# SparkFun_RTK_Facet_-_Main.net
KiCad netlist of a schematic drawn in EAGLE
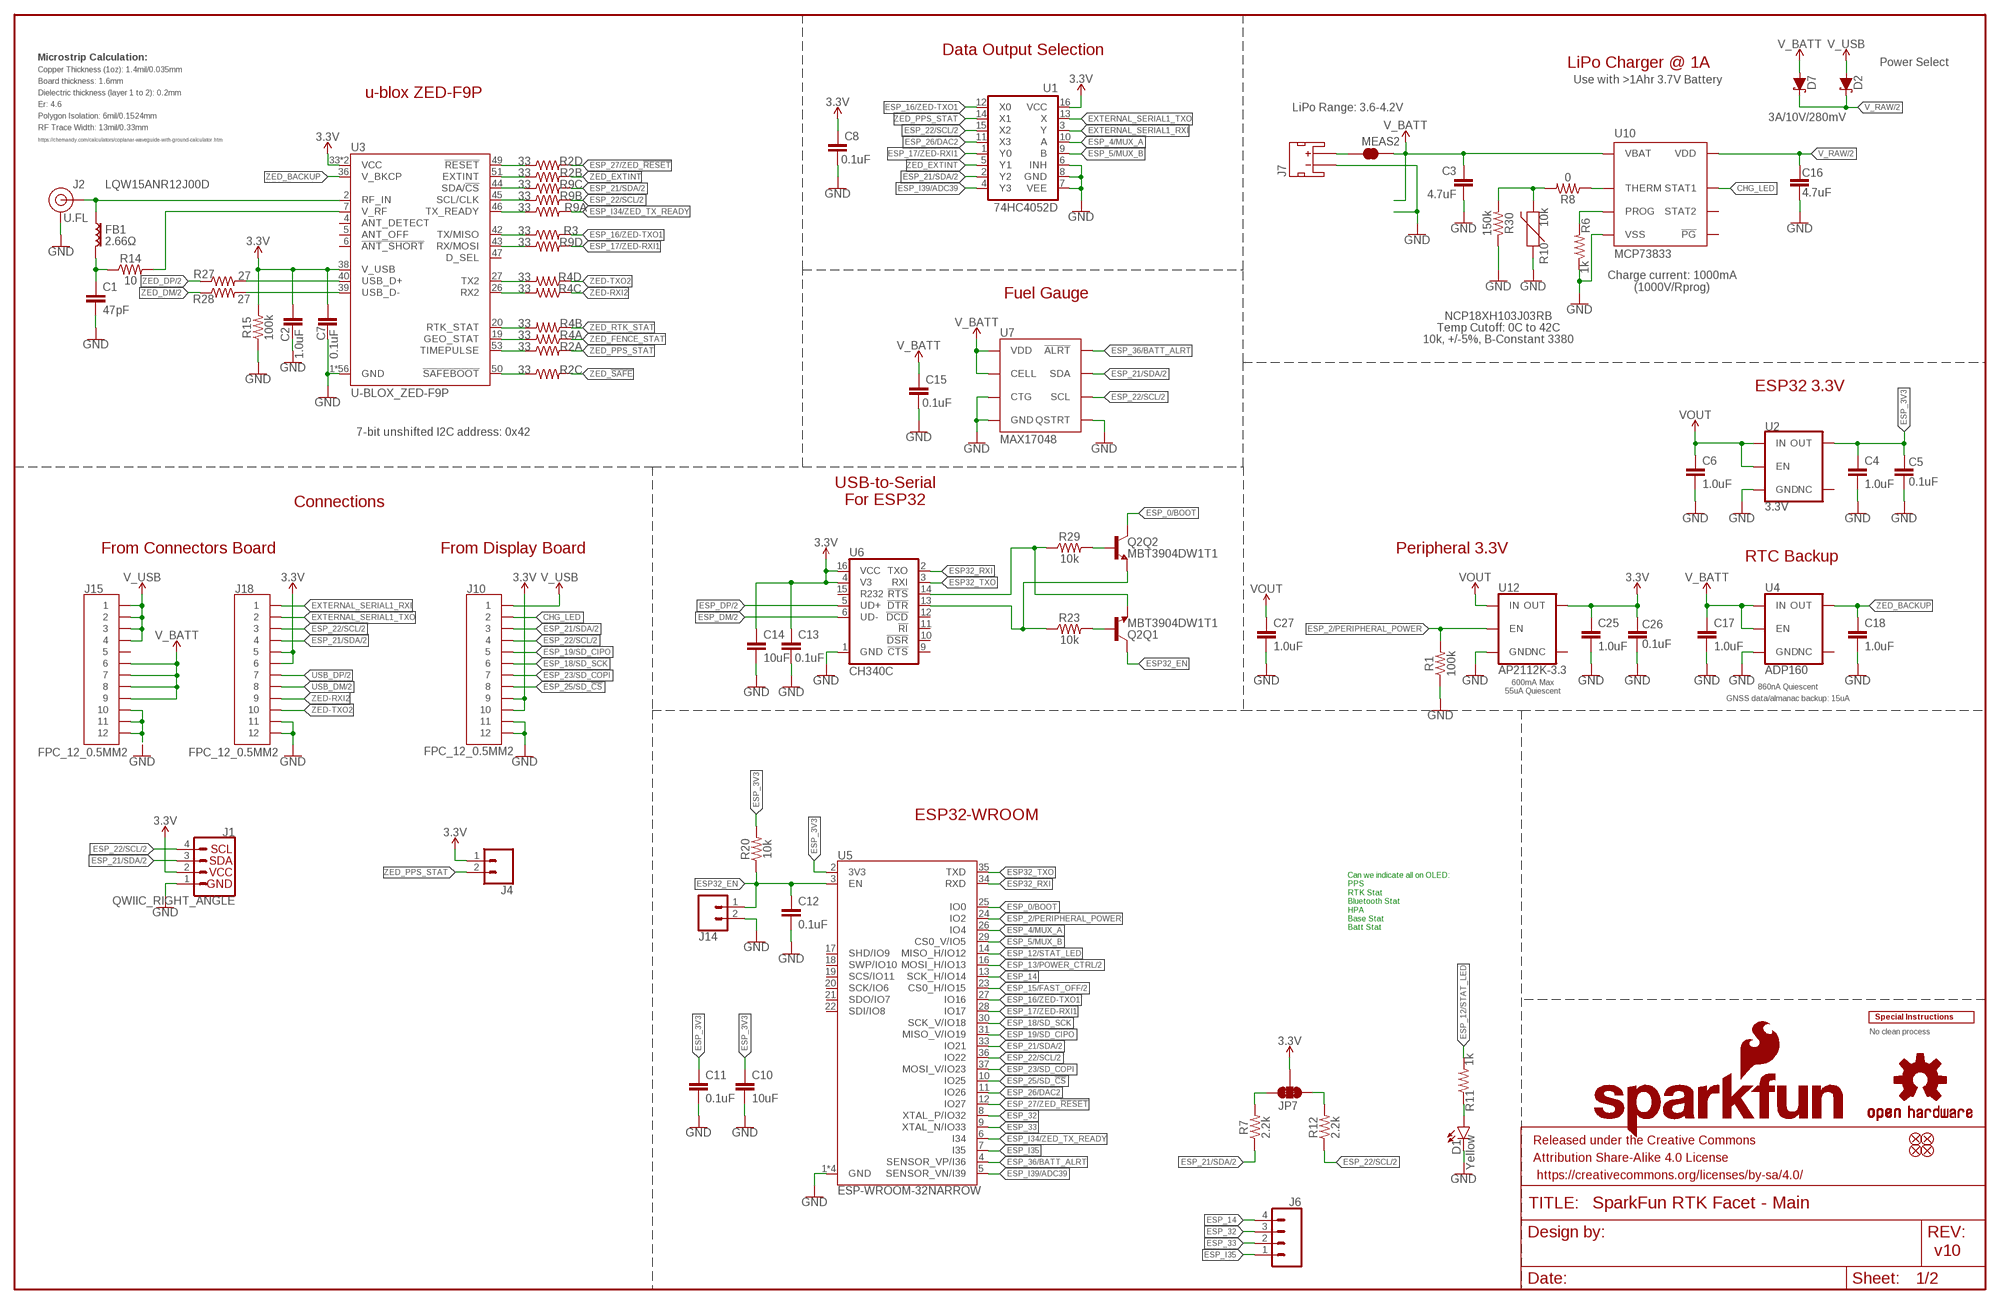
[diagram p0: schematic, sheet 1, part 1 of 2]
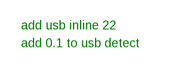
[diagram p1: schematic, sheet 1, part 2 of 2]
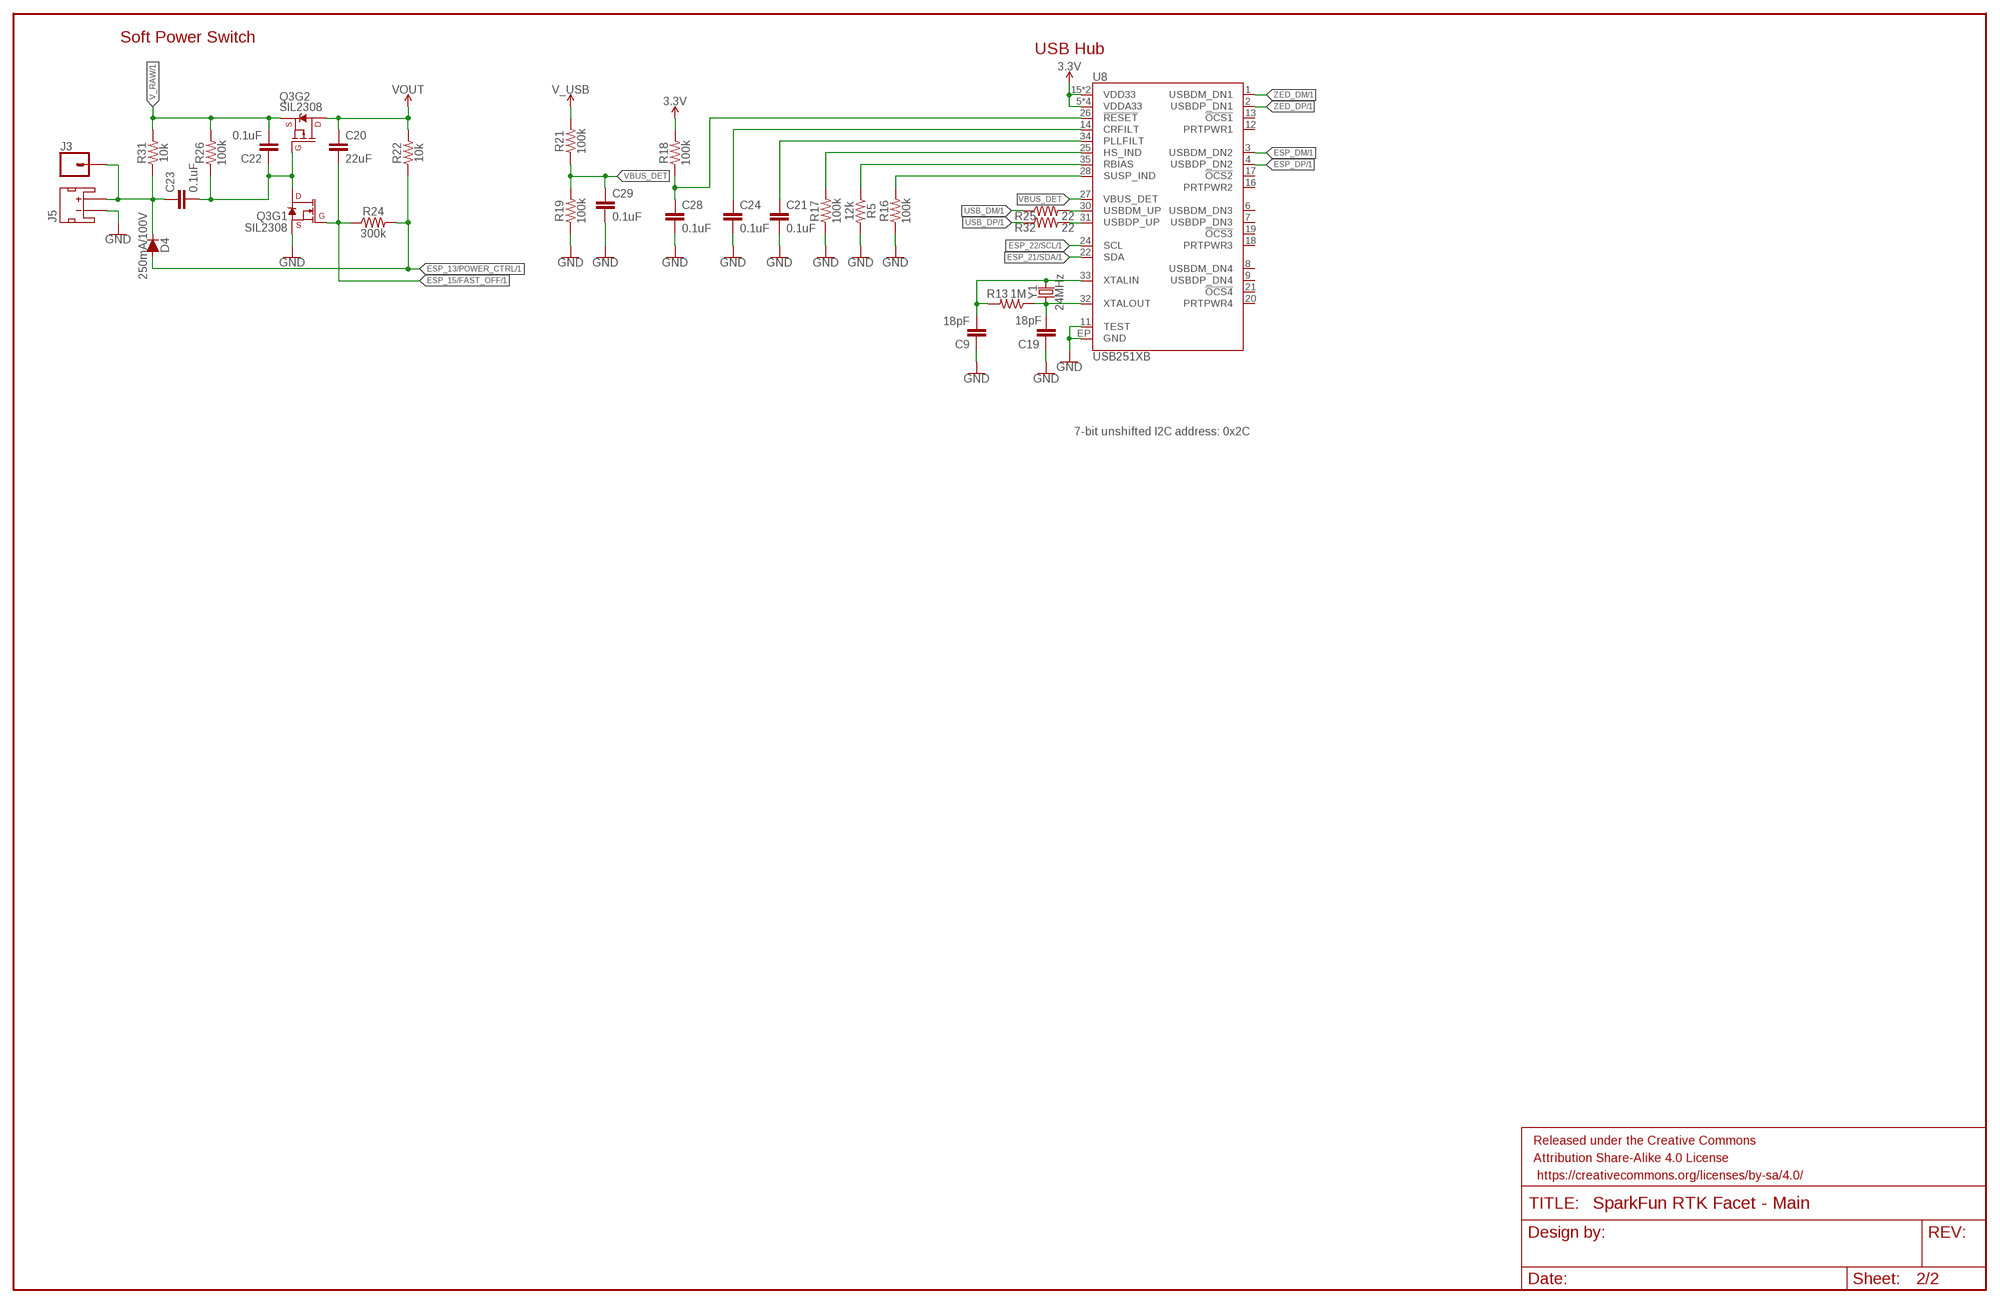
[diagram p2: schematic, sheet 2]

(export (version "E")
  (design (tool "Eeschema 10.0.6"))
  (components
    (comp (ref "C1")
      (value "47pF")
      (footprint "eagle-import:0402")
      (libsource (lib "eagle-import") (part "47PF-0402-25V-5%-X7R"))
    )
    (comp (ref "C2")
      (value "1.0uF")
      (footprint "eagle-import:0603")
      (libsource (lib "eagle-import") (part "1.0UF-0603-16V-10%-X7R"))
    )
    (comp (ref "C3")
      (value "4.7uF")
      (footprint "eagle-import:0603")
      (libsource (lib "eagle-import") (part "4.7UF-0603-35V-(20%)"))
    )
    (comp (ref "C4")
      (value "1.0uF")
      (footprint "eagle-import:0603")
      (libsource (lib "eagle-import") (part "1.0UF-0603-16V-10%-X7R"))
    )
    (comp (ref "C5")
      (value "0.1uF")
      (footprint "eagle-import:0603")
      (libsource (lib "eagle-import") (part "0.1UF-0603-25V-5%"))
    )
    (comp (ref "C6")
      (value "1.0uF")
      (footprint "eagle-import:0603")
      (libsource (lib "eagle-import") (part "1.0UF-0603-16V-10%-X7R"))
    )
    (comp (ref "C7")
      (value "0.1uF")
      (footprint "eagle-import:0603")
      (libsource (lib "eagle-import") (part "0.1UF-0603-25V-5%"))
    )
    (comp (ref "C8")
      (value "0.1uF")
      (footprint "eagle-import:0603")
      (libsource (lib "eagle-import") (part "0.1UF-0603-25V-(+80/-20%)"))
    )
    (comp (ref "C10")
      (value "10uF")
      (footprint "eagle-import:0603")
      (libsource (lib "eagle-import") (part "10UF-0603-6.3V-20%"))
    )
    (comp (ref "C11")
      (value "0.1uF")
      (footprint "eagle-import:0603")
      (libsource (lib "eagle-import") (part "0.1UF-0603-25V-(+80/-20%)"))
    )
    (comp (ref "C12")
      (value "0.1uF")
      (footprint "eagle-import:0603")
      (libsource (lib "eagle-import") (part "0.1UF-0603-25V-(+80/-20%)"))
    )
    (comp (ref "C13")
      (value "0.1uF")
      (footprint "eagle-import:0603")
      (libsource (lib "eagle-import") (part "0.1UF-0603-25V-(+80/-20%)"))
    )
    (comp (ref "C14")
      (value "10uF")
      (footprint "eagle-import:0603")
      (libsource (lib "eagle-import") (part "10UF-0603-6.3V-20%"))
    )
    (comp (ref "C15")
      (value "0.1uF")
      (footprint "eagle-import:0603")
      (libsource (lib "eagle-import") (part "0.1UF-0603-25V-(+80/-20%)"))
    )
    (comp (ref "C16")
      (value "4.7uF")
      (footprint "eagle-import:0603")
      (libsource (lib "eagle-import") (part "4.7UF-0603-35V-(20%)"))
    )
    (comp (ref "C17")
      (value "1.0uF")
      (footprint "eagle-import:0603")
      (libsource (lib "eagle-import") (part "1.0UF-0603-16V-10%-X7R"))
    )
    (comp (ref "C18")
      (value "1.0uF")
      (footprint "eagle-import:0603")
      (libsource (lib "eagle-import") (part "1.0UF-0603-16V-10%-X7R"))
    )
    (comp (ref "C25")
      (value "1.0uF")
      (footprint "eagle-import:0603")
      (libsource (lib "eagle-import") (part "1.0UF-0603-16V-10%-X7R"))
    )
    (comp (ref "C26")
      (value "0.1uF")
      (footprint "eagle-import:0603")
      (libsource (lib "eagle-import") (part "0.1UF-0603-25V-5%"))
    )
    (comp (ref "C27")
      (value "1.0uF")
      (footprint "eagle-import:0603")
      (libsource (lib "eagle-import") (part "1.0UF-0603-16V-10%-X7R"))
    )
    (comp (ref "D1")
      (value "Yellow")
      (footprint "eagle-import:LED-0603")
      (libsource (lib "eagle-import") (part "LED-YELLOW0603"))
    )
    (comp (ref "D2")
      (value "3A/10V/280mV")
      (footprint "eagle-import:SOD-323")
      (libsource (lib "eagle-import") (part "DIODE-SCHOTTKY-BAT60A"))
    )
    (comp (ref "D7")
      (value "3A/10V/280mV")
      (footprint "eagle-import:SOD-323")
      (libsource (lib "eagle-import") (part "DIODE-SCHOTTKY-BAT60A"))
    )
    (comp (ref "FB1")
      (value "2.66Ω")
      (footprint "eagle-import:0402-TIGHT")
      (libsource (lib "eagle-import") (part "FERRITE_BEAD-0402-2.66OHM-1GHZ"))
    )
    (comp (ref "FRAME2")
      (value "FRAME-LEDGER")
      (footprint "eagle-import:CREATIVE_COMMONS")
      (libsource (lib "eagle-import") (part "FRAME-LEDGER"))
    )
    (comp (ref "J1")
      (value "QWIIC_RIGHT_ANGLE")
      (footprint "eagle-import:JST04_1MM_RA")
      (libsource (lib "eagle-import") (part "QWIIC_CONNECTORJS-1MM"))
    )
    (comp (ref "J2")
      (value "U.FL")
      (footprint "eagle-import:U.FL")
      (libsource (lib "eagle-import") (part "U.FL2PIN"))
    )
    (comp (ref "J4")
      (value "CONN_021X02_NO_SILK")
      (footprint "eagle-import:1X02_NO_SILK")
      (libsource (lib "eagle-import") (part "CONN_021X02_NO_SILK"))
    )
    (comp (ref "J6")
      (value "CONN_041X04_NO_SILK_NO_POP")
      (footprint "eagle-import:1X04_NO_SILK")
      (libsource (lib "eagle-import") (part "CONN_041X04_NO_SILK_NO_POP"))
    )
    (comp (ref "J7")
      (value "JST_2MM_MALE")
      (footprint "eagle-import:JST-2-SMD")
      (libsource (lib "eagle-import") (part "JST_2MM_MALE"))
    )
    (comp (ref "J10")
      (value "FPC_12_0.5MM2")
      (footprint "eagle-import:FPC_12_FLIP_DOUBLESIDED_2")
      (libsource (lib "eagle-import") (part "FPC_12_0.5MM2"))
    )
    (comp (ref "J14")
      (value "CONN_021X02_NO_SILK")
      (footprint "eagle-import:1X02_NO_SILK")
      (libsource (lib "eagle-import") (part "CONN_021X02_NO_SILK"))
    )
    (comp (ref "J15")
      (value "FPC_12_0.5MM2")
      (footprint "eagle-import:FPC_12_FLIP_DOUBLESIDED_2")
      (libsource (lib "eagle-import") (part "FPC_12_0.5MM2"))
    )
    (comp (ref "J18")
      (value "FPC_12_0.5MM2")
      (footprint "eagle-import:FPC_12_FLIP_DOUBLESIDED_2")
      (libsource (lib "eagle-import") (part "FPC_12_0.5MM2"))
    )
    (comp (ref "JP7")
      (value "JUMPER-SMT_3_2-NC_TRACE_SILK")
      (footprint "eagle-import:SMT-JUMPER_3_2-NC_TRACE_SILK")
      (libsource (lib "eagle-import") (part "JUMPER-SMT_3_2-NC_TRACE_SILK"))
    )
    (comp (ref "JP21")
      (value "FIDUCIALUFIDUCIAL")
      (footprint "eagle-import:FIDUCIAL-MICRO")
      (libsource (lib "eagle-import") (part "FIDUCIALUFIDUCIAL"))
    )
    (comp (ref "JP61")
      (value "FIDUCIALUFIDUCIAL")
      (footprint "eagle-import:FIDUCIAL-MICRO")
      (libsource (lib "eagle-import") (part "FIDUCIALUFIDUCIAL"))
    )
    (comp (ref "JP71")
      (value "FIDUCIALUFIDUCIAL")
      (footprint "eagle-import:FIDUCIAL-MICRO")
      (libsource (lib "eagle-import") (part "FIDUCIALUFIDUCIAL"))
    )
    (comp (ref "JP81")
      (value "FIDUCIALUFIDUCIAL")
      (footprint "eagle-import:FIDUCIAL-MICRO")
      (libsource (lib "eagle-import") (part "FIDUCIALUFIDUCIAL"))
    )
    (comp (ref "LOGO1")
      (value "OSHW-LOGOMINI")
      (footprint "eagle-import:OSHW-LOGO-MINI")
      (libsource (lib "eagle-import") (part "OSHW-LOGOMINI"))
    )
    (comp (ref "LOGO2")
      (value "SFE_LOGO_NAME_FLAME.1_INCH")
      (footprint "eagle-import:SFE_LOGO_NAME_FLAME_.1")
      (libsource (lib "eagle-import") (part "SFE_LOGO_NAME_FLAME.1_INCH"))
    )
    (comp (ref "MEAS2")
      (value "JUMPER-COMBO_2_NC_TRACE")
      (footprint "eagle-import:COMBO-JUMPER_2_NC_TRACE")
      (libsource (lib "eagle-import") (part "JUMPER-COMBO_2_NC_TRACE"))
    )
    (comp (ref "Q2")
      (value "MBT3904DW1T1")
      (footprint "eagle-import:SC70-6")
      (libsource (lib "eagle-import") (part "TRANS_NPN_DUAL-MBT3904DW1T1"))
    )
    (comp (ref "R1")
      (value "100k")
      (footprint "eagle-import:0603")
      (libsource (lib "eagle-import") (part "100KOHM-0603-1/10W-1%"))
    )
    (comp (ref "R2")
      (value "33")
      (footprint "eagle-import:1206_RA")
      (libsource (lib "eagle-import") (part "33OHM_RA-1206-1/16W-5%"))
    )
    (comp (ref "R3")
      (value "33")
      (footprint "eagle-import:0603")
      (libsource (lib "eagle-import") (part "33OHM-0603-1/10W-1%"))
    )
    (comp (ref "R4")
      (value "33")
      (footprint "eagle-import:1206_RA")
      (libsource (lib "eagle-import") (part "33OHM_RA-1206-1/16W-5%"))
    )
    (comp (ref "R6")
      (value "1k")
      (footprint "eagle-import:0603")
      (libsource (lib "eagle-import") (part "1KOHM-0603-1/10W-1%"))
    )
    (comp (ref "R7")
      (value "2.2k")
      (footprint "eagle-import:0603")
      (libsource (lib "eagle-import") (part "2.2KOHM-0603-1/10W-1%"))
    )
    (comp (ref "R8")
      (value "0")
      (footprint "eagle-import:0603")
      (libsource (lib "eagle-import") (part "0OHM-0603-1/10W"))
    )
    (comp (ref "R9")
      (value "33")
      (footprint "eagle-import:1206_RA")
      (libsource (lib "eagle-import") (part "33OHM_RA-1206-1/16W-5%"))
    )
    (comp (ref "R10")
      (value "10k")
      (footprint "eagle-import:0603")
      (libsource (lib "eagle-import") (part "NTC-THERMISTOR-0603"))
    )
    (comp (ref "R11")
      (value "1k")
      (footprint "eagle-import:0603")
      (libsource (lib "eagle-import") (part "1KOHM-0603-1/10W-1%"))
    )
    (comp (ref "R12")
      (value "2.2k")
      (footprint "eagle-import:0603")
      (libsource (lib "eagle-import") (part "2.2KOHM-0603-1/10W-1%"))
    )
    (comp (ref "R14")
      (value "10")
      (footprint "eagle-import:0603")
      (libsource (lib "eagle-import") (part "10OHM-0603-1/10W-1%"))
    )
    (comp (ref "R15")
      (value "100k")
      (footprint "eagle-import:0603")
      (libsource (lib "eagle-import") (part "100KOHM-0603-1/10W-1%"))
    )
    (comp (ref "R20")
      (value "10k")
      (footprint "eagle-import:0603")
      (libsource (lib "eagle-import") (part "10KOHM-0603-1/10W-1%"))
    )
    (comp (ref "R23")
      (value "10k")
      (footprint "eagle-import:0603")
      (libsource (lib "eagle-import") (part "10KOHM-0603-1/10W-1%"))
    )
    (comp (ref "R27")
      (value "27")
      (footprint "eagle-import:0603")
      (libsource (lib "eagle-import") (part "27OHM-0603-1/10W-1%"))
    )
    (comp (ref "R28")
      (value "27")
      (footprint "eagle-import:0603")
      (libsource (lib "eagle-import") (part "27OHM-0603-1/10W-1%"))
    )
    (comp (ref "R29")
      (value "10k")
      (footprint "eagle-import:0603")
      (libsource (lib "eagle-import") (part "10KOHM-0603-1/10W-1%"))
    )
    (comp (ref "R30")
      (value "150k")
      (footprint "eagle-import:0603")
      (libsource (lib "eagle-import") (part "150KOHM-0603-1/10W-1%"))
    )
    (comp (ref "U$2")
      (value "SPECIAL_INSTRUCTIONS-ORDERING")
      (footprint "eagle-import:ORDERING_INSTRUCTIONS")
      (libsource (lib "eagle-import") (part "SPECIAL_INSTRUCTIONS-ORDERING"))
    )
    (comp (ref "U1")
      (value "74HC4052D")
      (footprint "eagle-import:SO16")
      (libsource (lib "eagle-import") (part "744052DHC"))
    )
    (comp (ref "U2")
      (value "3.3V")
      (footprint "eagle-import:SOT23-5")
      (libsource (lib "eagle-import") (part "V_REG_AP2112K-3.3V"))
    )
    (comp (ref "U3")
      (value "U-BLOX_ZED-F9P")
      (footprint "eagle-import:ZED-F9P")
      (libsource (lib "eagle-import") (part "U-BLOX_ZED-F9P"))
    )
    (comp (ref "U4")
      (value "ADP160")
      (footprint "eagle-import:SOT23-5")
      (libsource (lib "eagle-import") (part "ADP160"))
    )
    (comp (ref "U5")
      (value "ESP-WROOM-32NARROW")
      (footprint "eagle-import:ESP-WROOM-32-NARROW")
      (libsource (lib "eagle-import") (part "ESP-WROOM-32NARROW"))
    )
    (comp (ref "U6")
      (value "CH340C")
      (footprint "eagle-import:SO016")
      (libsource (lib "eagle-import") (part "CH340C"))
    )
    (comp (ref "U7")
      (value "MAX17048")
      (footprint "eagle-import:DFN-8")
      (libsource (lib "eagle-import") (part "MAX17048DFN8"))
    )
    (comp (ref "U10")
      (value "MCP73833")
      (footprint "eagle-import:DFN-10")
      (libsource (lib "eagle-import") (part "MCP73833"))
    )
    (comp (ref "U12")
      (value "AP2112K-3.3")
      (footprint "eagle-import:SOT23-5")
      (libsource (lib "eagle-import") (part "V_REG_AP2112K-3.3V"))
    )
    (comp (ref "C9")
      (value "18pF")
      (footprint "eagle-import:0603")
      (libsource (lib "eagle-import") (part "18PF-0603-50V-5%"))
    )
    (comp (ref "C19")
      (value "18pF")
      (footprint "eagle-import:0603")
      (libsource (lib "eagle-import") (part "18PF-0603-50V-5%"))
    )
    (comp (ref "C20")
      (value "22uF")
      (footprint "eagle-import:0603")
      (libsource (lib "eagle-import") (part "22UF-0603-6.3V-20%"))
    )
    (comp (ref "C21")
      (value "0.1uF")
      (footprint "eagle-import:0603")
      (libsource (lib "eagle-import") (part "0.1UF-0603-25V-5%"))
    )
    (comp (ref "C22")
      (value "0.1uF")
      (footprint "eagle-import:0603")
      (libsource (lib "eagle-import") (part "0.1UF-0603-25V-5%"))
    )
    (comp (ref "C23")
      (value "0.1uF")
      (footprint "eagle-import:0603")
      (libsource (lib "eagle-import") (part "0.1UF-0603-25V-5%"))
    )
    (comp (ref "C24")
      (value "0.1uF")
      (footprint "eagle-import:0603")
      (libsource (lib "eagle-import") (part "0.1UF-0603-25V-5%"))
    )
    (comp (ref "C28")
      (value "0.1uF")
      (footprint "eagle-import:0603")
      (libsource (lib "eagle-import") (part "0.1UF-0603-25V-5%"))
    )
    (comp (ref "C29")
      (value "0.1uF")
      (footprint "eagle-import:0603")
      (libsource (lib "eagle-import") (part "0.1UF-0603-25V-5%"))
    )
    (comp (ref "D4")
      (value "250mA/100V")
      (footprint "eagle-import:SOD-323")
      (libsource (lib "eagle-import") (part "DIODE-BAS16J"))
    )
    (comp (ref "FRAME1")
      (value "FRAME-LEDGER")
      (footprint "eagle-import:CREATIVE_COMMONS")
      (libsource (lib "eagle-import") (part "FRAME-LEDGER"))
    )
    (comp (ref "J3")
      (value "CONN_01PTH_NO_SILK_YES_STOP")
      (footprint "eagle-import:1X01_NO_SILK")
      (libsource (lib "eagle-import") (part "CONN_01PTH_NO_SILK_YES_STOP"))
    )
    (comp (ref "J5")
      (value "JST_2MM_MALE")
      (footprint "eagle-import:JST-2-SMD")
      (libsource (lib "eagle-import") (part "JST_2MM_MALE"))
    )
    (comp (ref "Q3")
      (value "SIL2308")
      (footprint "eagle-import:SOT26")
      (libsource (lib "eagle-import") (part "MOSFET_COMPLIMENTARY_PAIR-SIL2308"))
    )
    (comp (ref "R5")
      (value "12k")
      (footprint "eagle-import:0603")
      (libsource (lib "eagle-import") (part "12KOHM-0603-1/10W-1%"))
    )
    (comp (ref "R13")
      (value "1M")
      (footprint "eagle-import:0603")
      (libsource (lib "eagle-import") (part "1MOHM-0603-1/4W-5%"))
    )
    (comp (ref "R16")
      (value "100k")
      (footprint "eagle-import:0603")
      (libsource (lib "eagle-import") (part "100KOHM-0603-1/10W-1%"))
    )
    (comp (ref "R17")
      (value "100k")
      (footprint "eagle-import:0603")
      (libsource (lib "eagle-import") (part "100KOHM-0603-1/10W-1%"))
    )
    (comp (ref "R18")
      (value "100k")
      (footprint "eagle-import:0603")
      (libsource (lib "eagle-import") (part "100KOHM-0603-1/10W-1%"))
    )
    (comp (ref "R19")
      (value "100k")
      (footprint "eagle-import:0603")
      (libsource (lib "eagle-import") (part "100KOHM-0603-1/10W-1%"))
    )
    (comp (ref "R21")
      (value "100k")
      (footprint "eagle-import:0603")
      (libsource (lib "eagle-import") (part "100KOHM-0603-1/10W-1%"))
    )
    (comp (ref "R22")
      (value "10k")
      (footprint "eagle-import:0603")
      (libsource (lib "eagle-import") (part "10KOHM-0603-1/10W-1%"))
    )
    (comp (ref "R24")
      (value "300k")
      (footprint "eagle-import:0603")
      (libsource (lib "eagle-import") (part "300KOHM-0603-1/10W-1%"))
    )
    (comp (ref "R25")
      (value "22")
      (footprint "eagle-import:0603")
      (libsource (lib "eagle-import") (part "22OHM-0603-1/10W-1%"))
    )
    (comp (ref "R26")
      (value "100k")
      (footprint "eagle-import:0603")
      (libsource (lib "eagle-import") (part "100KOHM-0603-1/10W-1%"))
    )
    (comp (ref "R31")
      (value "10k")
      (footprint "eagle-import:0603")
      (libsource (lib "eagle-import") (part "10KOHM-0603-1/10W-1%"))
    )
    (comp (ref "R32")
      (value "22")
      (footprint "eagle-import:0603")
      (libsource (lib "eagle-import") (part "22OHM-0603-1/10W-1%"))
    )
    (comp (ref "U8")
      (value "USB251XB")
      (footprint "eagle-import:QFN-36")
      (libsource (lib "eagle-import") (part "USB251XB"))
    )
    (comp (ref "Y1")
      (value "24MHz")
      (footprint "eagle-import:CRYSTAL-SMD-2.0X1.6MM")
      (libsource (lib "eagle-import") (part "CRYSTAL-24MHZ-SMD-2.0X1.6MM"))
    )
  )
  (nets
    (net (code "1") (name "3.3V") (class "Default")
      (node (ref "C13") (pin "1") (pinfunction "1_1") (pintype "passive"))
      (node (ref "C14") (pin "1") (pinfunction "1_1") (pintype "passive"))
      (node (ref "C2") (pin "1") (pinfunction "1_1") (pintype "passive"))
      (node (ref "C25") (pin "1") (pinfunction "1_1") (pintype "passive"))
      (node (ref "C26") (pin "2") (pinfunction "2_2") (pintype "passive"))
      (node (ref "C7") (pin "2") (pinfunction "2_2") (pintype "passive"))
      (node (ref "C8") (pin "1") (pinfunction "1_1") (pintype "passive"))
      (node (ref "J1") (pin "2") (pinfunction "2_2") (pintype "power_in"))
      (node (ref "J10") (pin "10") (pinfunction "10_10") (pintype "bidirectional"))
      (node (ref "J10") (pin "9") (pinfunction "9_9") (pintype "bidirectional"))
      (node (ref "J18") (pin "5") (pinfunction "5_5") (pintype "bidirectional"))
      (node (ref "J18") (pin "6") (pinfunction "6_6") (pintype "bidirectional"))
      (node (ref "J4") (pin "1") (pinfunction "1_1") (pintype "passive"))
      (node (ref "JP7") (pin "2") (pinfunction "2_2") (pintype "passive"))
      (node (ref "R15") (pin "2") (pinfunction "2_2") (pintype "passive"))
      (node (ref "R18") (pin "2") (pinfunction "2_2") (pintype "passive"))
      (node (ref "U1") (pin "16") (pinfunction "VCC_16") (pintype "power_in"))
      (node (ref "U12") (pin "5") (pinfunction "OUT_5") (pintype "passive"))
      (node (ref "U3") (pin "33") (pinfunction "VCC_33") (pintype "bidirectional"))
      (node (ref "U3") (pin "34") (pinfunction "VCC_34") (pintype "bidirectional"))
      (node (ref "U3") (pin "38") (pinfunction "V_USB_38") (pintype "bidirectional"))
      (node (ref "U6") (pin "16") (pinfunction "VCC_16") (pintype "bidirectional"))
      (node (ref "U6") (pin "4") (pinfunction "V3_4") (pintype "bidirectional"))
      (node (ref "U8") (pin "10") (pinfunction "VDDA33_10") (pintype "bidirectional"))
      (node (ref "U8") (pin "15") (pinfunction "VDD33_15") (pintype "bidirectional"))
      (node (ref "U8") (pin "23") (pinfunction "VDD33_23") (pintype "bidirectional"))
      (node (ref "U8") (pin "29") (pinfunction "VDDA33_29") (pintype "bidirectional"))
      (node (ref "U8") (pin "36") (pinfunction "VDDA33_36") (pintype "bidirectional"))
      (node (ref "U8") (pin "5") (pinfunction "VDDA33_5") (pintype "bidirectional"))
    )
    (net (code "2") (name "CHG_LED") (class "Default")
      (node (ref "J10") (pin "2") (pinfunction "2_2") (pintype "bidirectional"))
      (node (ref "U10") (pin "3") (pinfunction "STAT1_3") (pintype "bidirectional"))
    )
    (net (code "3") (name "ESP32_EN") (class "Default")
      (node (ref "C12") (pin "1") (pinfunction "1_1") (pintype "passive"))
      (node (ref "J14") (pin "1") (pinfunction "1_1") (pintype "passive"))
      (node (ref "Q2") (pin "3") (pinfunction "C_3") (pintype "passive"))
      (node (ref "R20") (pin "1") (pinfunction "1_1") (pintype "passive"))
      (node (ref "U5") (pin "3") (pinfunction "EN_3") (pintype "bidirectional"))
    )
    (net (code "4") (name "ESP32_RXI") (class "Default")
      (node (ref "U5") (pin "34") (pinfunction "RXD_34") (pintype "bidirectional"))
      (node (ref "U6") (pin "2") (pinfunction "TXO_2") (pintype "bidirectional"))
    )
    (net (code "5") (name "ESP32_TXO") (class "Default")
      (node (ref "U5") (pin "35") (pinfunction "TXD_35") (pintype "bidirectional"))
      (node (ref "U6") (pin "3") (pinfunction "RXI_3") (pintype "bidirectional"))
    )
    (net (code "6") (name "ESP_0{slash}BOOT") (class "Default")
      (node (ref "Q2") (pin "6") (pinfunction "C_6") (pintype "passive"))
      (node (ref "U5") (pin "25") (pinfunction "IO0_25") (pintype "bidirectional"))
    )
    (net (code "7") (name "ESP_2{slash}PERIPHERAL_POWER") (class "Default")
      (node (ref "R1") (pin "2") (pinfunction "2_2") (pintype "passive"))
      (node (ref "U12") (pin "3") (pinfunction "EN_3") (pintype "input"))
      (node (ref "U5") (pin "24") (pinfunction "IO2_24") (pintype "bidirectional"))
    )
    (net (code "8") (name "ESP_3V3") (class "Default")
      (node (ref "C10") (pin "1") (pinfunction "1_1") (pintype "passive"))
      (node (ref "C11") (pin "1") (pinfunction "1_1") (pintype "passive"))
      (node (ref "C4") (pin "1") (pinfunction "1_1") (pintype "passive"))
      (node (ref "C5") (pin "2") (pinfunction "2_2") (pintype "passive"))
      (node (ref "R20") (pin "2") (pinfunction "2_2") (pintype "passive"))
      (node (ref "U2") (pin "5") (pinfunction "OUT_5") (pintype "passive"))
      (node (ref "U5") (pin "2") (pinfunction "3V3_2") (pintype "bidirectional"))
    )
    (net (code "9") (name "ESP_4{slash}MUX_A") (class "Default")
      (node (ref "U1") (pin "10") (pinfunction "A_10") (pintype "input"))
      (node (ref "U5") (pin "26") (pinfunction "IO4_26") (pintype "bidirectional"))
    )
    (net (code "10") (name "ESP_5{slash}MUX_B") (class "Default")
      (node (ref "U1") (pin "9") (pinfunction "B_9") (pintype "input"))
      (node (ref "U5") (pin "29") (pinfunction "CS0_V/IO5_29") (pintype "bidirectional"))
    )
    (net (code "11") (name "ESP_12{slash}STAT_LED") (class "Default")
      (node (ref "R11") (pin "2") (pinfunction "2_2") (pintype "passive"))
      (node (ref "U5") (pin "14") (pinfunction "MISO_H/IO12_14") (pintype "bidirectional"))
    )
    (net (code "12") (name "ESP_13{slash}POWER_CTRL") (class "Default")
      (node (ref "D4") (pin "A") (pinfunction "A_A") (pintype "passive"))
      (node (ref "R22") (pin "1") (pinfunction "1_1") (pintype "passive"))
      (node (ref "R24") (pin "2") (pinfunction "2_2") (pintype "passive"))
      (node (ref "U5") (pin "16") (pinfunction "MOSI_H/IO13_16") (pintype "bidirectional"))
    )
    (net (code "13") (name "ESP_14") (class "Default")
      (node (ref "J6") (pin "4") (pinfunction "4_4") (pintype "passive"))
      (node (ref "U5") (pin "13") (pinfunction "SCK_H/IO14_13") (pintype "bidirectional"))
    )
    (net (code "14") (name "ESP_15{slash}FAST_OFF") (class "Default")
      (node (ref "C20") (pin "2") (pinfunction "2_2") (pintype "passive"))
      (node (ref "Q3") (pin "G1") (pinfunction "G_G1") (pintype "bidirectional"))
      (node (ref "R24") (pin "1") (pinfunction "1_1") (pintype "passive"))
      (node (ref "U5") (pin "23") (pinfunction "CS0_H/IO15_23") (pintype "bidirectional"))
    )
    (net (code "15") (name "ESP_16{slash}ZED-TXO1") (class "Default")
      (node (ref "R3") (pin "2") (pinfunction "2_2") (pintype "passive"))
      (node (ref "U1") (pin "12") (pinfunction "X0_12") (pintype "bidirectional"))
      (node (ref "U5") (pin "27") (pinfunction "IO16_27") (pintype "bidirectional"))
    )
    (net (code "16") (name "ESP_17{slash}ZED-RXI1") (class "Default")
      (node (ref "R9") (pin "P5") (pinfunction "2_P5") (pintype "passive"))
      (node (ref "U1") (pin "1") (pinfunction "Y0_1") (pintype "bidirectional"))
      (node (ref "U5") (pin "28") (pinfunction "IO17_28") (pintype "bidirectional"))
    )
    (net (code "17") (name "ESP_18{slash}SD_SCK") (class "Default")
      (node (ref "J10") (pin "6") (pinfunction "6_6") (pintype "bidirectional"))
      (node (ref "U5") (pin "30") (pinfunction "SCK_V/IO18_30") (pintype "bidirectional"))
    )
    (net (code "18") (name "ESP_19{slash}SD_CIPO") (class "Default")
      (node (ref "J10") (pin "5") (pinfunction "5_5") (pintype "bidirectional"))
      (node (ref "U5") (pin "31") (pinfunction "MISO_V/IO19_31") (pintype "bidirectional"))
    )
    (net (code "19") (name "ESP_21{slash}SDA") (class "Default")
      (node (ref "J1") (pin "3") (pinfunction "3_3") (pintype "passive"))
      (node (ref "J10") (pin "3") (pinfunction "3_3") (pintype "bidirectional"))
      (node (ref "J18") (pin "4") (pinfunction "4_4") (pintype "bidirectional"))
      (node (ref "R7") (pin "1") (pinfunction "1_1") (pintype "passive"))
      (node (ref "R9") (pin "P6") (pinfunction "2_P6") (pintype "passive"))
      (node (ref "U1") (pin "2") (pinfunction "Y2_2") (pintype "bidirectional"))
      (node (ref "U5") (pin "33") (pinfunction "IO21_33") (pintype "bidirectional"))
      (node (ref "U7") (pin "8") (pinfunction "SDA_8") (pintype "input"))
      (node (ref "U8") (pin "22") (pinfunction "SDA_22") (pintype "bidirectional"))
    )
    (net (code "20") (name "ESP_22{slash}SCL") (class "Default")
      (node (ref "J1") (pin "4") (pinfunction "4_4") (pintype "passive"))
      (node (ref "J10") (pin "4") (pinfunction "4_4") (pintype "bidirectional"))
      (node (ref "J18") (pin "3") (pinfunction "3_3") (pintype "bidirectional"))
      (node (ref "R12") (pin "1") (pinfunction "1_1") (pintype "passive"))
      (node (ref "R9") (pin "P7") (pinfunction "2_P7") (pintype "passive"))
      (node (ref "U1") (pin "15") (pinfunction "X2_15") (pintype "bidirectional"))
      (node (ref "U5") (pin "36") (pinfunction "IO22_36") (pintype "bidirectional"))
      (node (ref "U7") (pin "7") (pinfunction "SCL_7") (pintype "output"))
      (node (ref "U8") (pin "24") (pinfunction "SCL_24") (pintype "bidirectional"))
    )
    (net (code "21") (name "ESP_23{slash}SD_COPI") (class "Default")
      (node (ref "J10") (pin "7") (pinfunction "7_7") (pintype "bidirectional"))
      (node (ref "U5") (pin "37") (pinfunction "MOSI_V/IO23_37") (pintype "bidirectional"))
    )
    (net (code "22") (name "ESP_25{slash}SD_~{CS}") (class "Default")
      (node (ref "J10") (pin "8") (pinfunction "8_8") (pintype "bidirectional"))
      (node (ref "U5") (pin "10") (pinfunction "IO25_10") (pintype "bidirectional"))
    )
    (net (code "23") (name "ESP_26{slash}DAC2") (class "Default")
      (node (ref "U1") (pin "11") (pinfunction "X3_11") (pintype "bidirectional"))
      (node (ref "U5") (pin "11") (pinfunction "IO26_11") (pintype "bidirectional"))
    )
    (net (code "24") (name "ESP_27{slash}ZED_~{RESET}") (class "Default")
      (node (ref "R2") (pin "P5") (pinfunction "2_P5") (pintype "passive"))
      (node (ref "U5") (pin "12") (pinfunction "IO27_12") (pintype "bidirectional"))
    )
    (net (code "25") (name "ESP_32") (class "Default")
      (node (ref "J6") (pin "3") (pinfunction "3_3") (pintype "passive"))
      (node (ref "U5") (pin "8") (pinfunction "XTAL_P/IO32_8") (pintype "bidirectional"))
    )
    (net (code "26") (name "ESP_33") (class "Default")
      (node (ref "J6") (pin "2") (pinfunction "2_2") (pintype "passive"))
      (node (ref "U5") (pin "9") (pinfunction "XTAL_N/IO33_9") (pintype "bidirectional"))
    )
    (net (code "27") (name "ESP_36{slash}BATT_ALRT") (class "Default")
      (node (ref "U5") (pin "4") (pinfunction "SENSOR_VP/I36_4") (pintype "bidirectional"))
      (node (ref "U7") (pin "5") (pinfunction "~{ALRT}_5") (pintype "bidirectional"))
    )
    (net (code "28") (name "ESP_DM") (class "Default")
      (node (ref "U6") (pin "6") (pinfunction "UD-_6") (pintype "bidirectional"))
      (node (ref "U8") (pin "3") (pinfunction "USBDM_DN2_3") (pintype "bidirectional"))
    )
    (net (code "29") (name "ESP_DP") (class "Default")
      (node (ref "U6") (pin "5") (pinfunction "UD+_5") (pintype "bidirectional"))
      (node (ref "U8") (pin "4") (pinfunction "USBDP_DN2_4") (pintype "bidirectional"))
    )
    (net (code "30") (name "ESP_I34{slash}ZED_TX_READY") (class "Default")
      (node (ref "R9") (pin "P8") (pinfunction "2_P8") (pintype "passive"))
      (node (ref "U5") (pin "6") (pinfunction "I34_6") (pintype "bidirectional"))
    )
    (net (code "31") (name "ESP_I35") (class "Default")
      (node (ref "J6") (pin "1") (pinfunction "1_1") (pintype "passive"))
      (node (ref "U5") (pin "7") (pinfunction "I35_7") (pintype "bidirectional"))
    )
    (net (code "32") (name "ESP_I39{slash}ADC39") (class "Default")
      (node (ref "U1") (pin "4") (pinfunction "Y3_4") (pintype "bidirectional"))
      (node (ref "U5") (pin "5") (pinfunction "SENSOR_VN/I39_5") (pintype "bidirectional"))
    )
    (net (code "33") (name "EXTERNAL_SERIAL1_RXI") (class "Default")
      (node (ref "J18") (pin "1") (pinfunction "1_1") (pintype "bidirectional"))
      (node (ref "U1") (pin "3") (pinfunction "Y_3") (pintype "bidirectional"))
    )
    (net (code "34") (name "EXTERNAL_SERIAL1_TXO") (class "Default")
      (node (ref "J18") (pin "2") (pinfunction "2_2") (pintype "bidirectional"))
      (node (ref "U1") (pin "13") (pinfunction "X_13") (pintype "bidirectional"))
    )
    (net (code "35") (name "GND") (class "Default")
      (node (ref "C1") (pin "2") (pinfunction "2_2") (pintype "passive"))
      (node (ref "C10") (pin "2") (pinfunction "2_2") (pintype "passive"))
      (node (ref "C11") (pin "2") (pinfunction "2_2") (pintype "passive"))
      (node (ref "C12") (pin "2") (pinfunction "2_2") (pintype "passive"))
      (node (ref "C13") (pin "2") (pinfunction "2_2") (pintype "passive"))
      (node (ref "C14") (pin "2") (pinfunction "2_2") (pintype "passive"))
      (node (ref "C15") (pin "2") (pinfunction "2_2") (pintype "passive"))
      (node (ref "C16") (pin "2") (pinfunction "2_2") (pintype "passive"))
      (node (ref "C17") (pin "2") (pinfunction "2_2") (pintype "passive"))
      (node (ref "C18") (pin "2") (pinfunction "2_2") (pintype "passive"))
      (node (ref "C19") (pin "1") (pinfunction "1_1") (pintype "passive"))
      (node (ref "C2") (pin "2") (pinfunction "2_2") (pintype "passive"))
      (node (ref "C21") (pin "2") (pinfunction "2_2") (pintype "passive"))
      (node (ref "C24") (pin "2") (pinfunction "2_2") (pintype "passive"))
      (node (ref "C25") (pin "2") (pinfunction "2_2") (pintype "passive"))
      (node (ref "C26") (pin "1") (pinfunction "1_1") (pintype "passive"))
      (node (ref "C27") (pin "2") (pinfunction "2_2") (pintype "passive"))
      (node (ref "C28") (pin "2") (pinfunction "2_2") (pintype "passive"))
      (node (ref "C29") (pin "2") (pinfunction "2_2") (pintype "passive"))
      (node (ref "C3") (pin "2") (pinfunction "2_2") (pintype "passive"))
      (node (ref "C4") (pin "2") (pinfunction "2_2") (pintype "passive"))
      (node (ref "C5") (pin "1") (pinfunction "1_1") (pintype "passive"))
      (node (ref "C6") (pin "2") (pinfunction "2_2") (pintype "passive"))
      (node (ref "C7") (pin "1") (pinfunction "1_1") (pintype "passive"))
      (node (ref "C8") (pin "2") (pinfunction "2_2") (pintype "passive"))
      (node (ref "C9") (pin "1") (pinfunction "1_1") (pintype "passive"))
      (node (ref "D1") (pin "C") (pinfunction "C_C") (pintype "passive"))
      (node (ref "J1") (pin "1") (pinfunction "1_1") (pintype "power_in"))
      (node (ref "J10") (pin "11") (pinfunction "11_11") (pintype "bidirectional"))
      (node (ref "J10") (pin "12") (pinfunction "12_12") (pintype "bidirectional"))
      (node (ref "J14") (pin "2") (pinfunction "2_2") (pintype "passive"))
      (node (ref "J15") (pin "10") (pinfunction "10_10") (pintype "bidirectional"))
      (node (ref "J15") (pin "11") (pinfunction "11_11") (pintype "bidirectional"))
      (node (ref "J15") (pin "12") (pinfunction "12_12") (pintype "bidirectional"))
      (node (ref "J18") (pin "11") (pinfunction "11_11") (pintype "bidirectional"))
      (node (ref "J18") (pin "12") (pinfunction "12_12") (pintype "bidirectional"))
      (node (ref "J2") (pin "1") (pinfunction "GND_1") (pintype "bidirectional"))
      (node (ref "J2") (pin "2") (pinfunction "GND_2") (pintype "bidirectional"))
      (node (ref "J5") (pin "1") (pinfunction "-_1") (pintype "bidirectional"))
      (node (ref "J7") (pin "1") (pinfunction "-_1") (pintype "bidirectional"))
      (node (ref "Q3") (pin "S1") (pinfunction "S_S1") (pintype "bidirectional"))
      (node (ref "R1") (pin "1") (pinfunction "1_1") (pintype "passive"))
      (node (ref "R10") (pin "1") (pinfunction "1_1") (pintype "bidirectional"))
      (node (ref "R15") (pin "1") (pinfunction "1_1") (pintype "passive"))
      (node (ref "R16") (pin "1") (pinfunction "1_1") (pintype "passive"))
      (node (ref "R17") (pin "1") (pinfunction "1_1") (pintype "passive"))
      (node (ref "R19") (pin "1") (pinfunction "1_1") (pintype "passive"))
      (node (ref "R30") (pin "1") (pinfunction "1_1") (pintype "passive"))
      (node (ref "R5") (pin "2") (pinfunction "2_2") (pintype "passive"))
      (node (ref "R6") (pin "1") (pinfunction "1_1") (pintype "passive"))
      (node (ref "U1") (pin "6") (pinfunction "INH_6") (pintype "input"))
      (node (ref "U1") (pin "7") (pinfunction "VEE_7") (pintype "power_in"))
      (node (ref "U1") (pin "8") (pinfunction "GND_8") (pintype "power_in"))
      (node (ref "U10") (pin "11") (pinfunction "VSS_11") (pintype "bidirectional"))
      (node (ref "U10") (pin "5") (pinfunction "VSS_5") (pintype "bidirectional"))
      (node (ref "U12") (pin "2") (pinfunction "GND_2") (pintype "input"))
      (node (ref "U2") (pin "2") (pinfunction "GND_2") (pintype "input"))
      (node (ref "U3") (pin "1") (pinfunction "GND_1") (pintype "bidirectional"))
      (node (ref "U3") (pin "100") (pinfunction "GND_100") (pintype "bidirectional"))
      (node (ref "U3") (pin "101") (pinfunction "GND_101") (pintype "bidirectional"))
      (node (ref "U3") (pin "102") (pinfunction "GND_102") (pintype "bidirectional"))
      (node (ref "U3") (pin "12") (pinfunction "GND_12") (pintype "bidirectional"))
      (node (ref "U3") (pin "14") (pinfunction "GND_14") (pintype "bidirectional"))
      (node (ref "U3") (pin "3") (pinfunction "GND_3") (pintype "bidirectional"))
      (node (ref "U3") (pin "32") (pinfunction "GND_32") (pintype "bidirectional"))
      (node (ref "U3") (pin "37") (pinfunction "GND_37") (pintype "bidirectional"))
      (node (ref "U3") (pin "41") (pinfunction "GND_41") (pintype "bidirectional"))
      (node (ref "U3") (pin "48") (pinfunction "GND_48") (pintype "bidirectional"))
      (node (ref "U3") (pin "55") (pinfunction "GND_55") (pintype "bidirectional"))
      (node (ref "U3") (pin "56") (pinfunction "GND_56") (pintype "bidirectional"))
      (node (ref "U3") (pin "57") (pinfunction "GND_57") (pintype "bidirectional"))
      (node (ref "U3") (pin "58") (pinfunction "GND_58") (pintype "bidirectional"))
      (node (ref "U3") (pin "59") (pinfunction "GND_59") (pintype "bidirectional"))
      (node (ref "U3") (pin "60") (pinfunction "GND_60") (pintype "bidirectional"))
      (node (ref "U3") (pin "61") (pinfunction "GND_61") (pintype "bidirectional"))
      (node (ref "U3") (pin "62") (pinfunction "GND_62") (pintype "bidirectional"))
      (node (ref "U3") (pin "63") (pinfunction "GND_63") (pintype "bidirectional"))
      (node (ref "U3") (pin "64") (pinfunction "GND_64") (pintype "bidirectional"))
      (node (ref "U3") (pin "65") (pinfunction "GND_65") (pintype "bidirectional"))
      (node (ref "U3") (pin "66") (pinfunction "GND_66") (pintype "bidirectional"))
      (node (ref "U3") (pin "67") (pinfunction "GND_67") (pintype "bidirectional"))
      (node (ref "U3") (pin "68") (pinfunction "GND_68") (pintype "bidirectional"))
      (node (ref "U3") (pin "69") (pinfunction "GND_69") (pintype "bidirectional"))
      (node (ref "U3") (pin "70") (pinfunction "GND_70") (pintype "bidirectional"))
      (node (ref "U3") (pin "71") (pinfunction "GND_71") (pintype "bidirectional"))
      (node (ref "U3") (pin "72") (pinfunction "GND_72") (pintype "bidirectional"))
      (node (ref "U3") (pin "73") (pinfunction "GND_73") (pintype "bidirectional"))
      (node (ref "U3") (pin "74") (pinfunction "GND_74") (pintype "bidirectional"))
      (node (ref "U3") (pin "75") (pinfunction "GND_75") (pintype "bidirectional"))
      (node (ref "U3") (pin "76") (pinfunction "GND_76") (pintype "bidirectional"))
      (node (ref "U3") (pin "77") (pinfunction "GND_77") (pintype "bidirectional"))
      (node (ref "U3") (pin "78") (pinfunction "GND_78") (pintype "bidirectional"))
      (node (ref "U3") (pin "79") (pinfunction "GND_79") (pintype "bidirectional"))
      (node (ref "U3") (pin "80") (pinfunction "GND_80") (pintype "bidirectional"))
      (node (ref "U3") (pin "81") (pinfunction "GND_81") (pintype "bidirectional"))
      (node (ref "U3") (pin "82") (pinfunction "GND_82") (pintype "bidirectional"))
      (node (ref "U3") (pin "83") (pinfunction "GND_83") (pintype "bidirectional"))
      (node (ref "U3") (pin "84") (pinfunction "GND_84") (pintype "bidirectional"))
      (node (ref "U3") (pin "85") (pinfunction "GND_85") (pintype "bidirectional"))
      (node (ref "U3") (pin "86") (pinfunction "GND_86") (pintype "bidirectional"))
      (node (ref "U3") (pin "87") (pinfunction "GND_87") (pintype "bidirectional"))
      (node (ref "U3") (pin "88") (pinfunction "GND_88") (pintype "bidirectional"))
      (node (ref "U3") (pin "89") (pinfunction "GND_89") (pintype "bidirectional"))
      (node (ref "U3") (pin "90") (pinfunction "GND_90") (pintype "bidirectional"))
      (node (ref "U3") (pin "91") (pinfunction "GND_91") (pintype "bidirectional"))
      (node (ref "U3") (pin "92") (pinfunction "GND_92") (pintype "bidirectional"))
      (node (ref "U3") (pin "93") (pinfunction "GND_93") (pintype "bidirectional"))
      (node (ref "U3") (pin "94") (pinfunction "GND_94") (pintype "bidirectional"))
      (node (ref "U3") (pin "95") (pinfunction "GND_95") (pintype "bidirectional"))
      (node (ref "U3") (pin "96") (pinfunction "GND_96") (pintype "bidirectional"))
      (node (ref "U3") (pin "97") (pinfunction "GND_97") (pintype "bidirectional"))
      (node (ref "U3") (pin "98") (pinfunction "GND_98") (pintype "bidirectional"))
      (node (ref "U3") (pin "99") (pinfunction "GND_99") (pintype "bidirectional"))
      (node (ref "U4") (pin "2") (pinfunction "GND_2") (pintype "input"))
      (node (ref "U5") (pin "1") (pinfunction "GND_1") (pintype "bidirectional"))
      (node (ref "U5") (pin "15") (pinfunction "GND_15") (pintype "bidirectional"))
      (node (ref "U5") (pin "38") (pinfunction "GND_38") (pintype "bidirectional"))
      (node (ref "U5") (pin "GND") (pinfunction "GND_GND") (pintype "bidirectional"))
      (node (ref "U6") (pin "1") (pinfunction "GND_1") (pintype "bidirectional"))
      (node (ref "U7") (pin "1") (pinfunction "CTG_1") (pintype "input"))
      (node (ref "U7") (pin "4") (pinfunction "GND_4") (pintype "bidirectional"))
      (node (ref "U7") (pin "6") (pinfunction "QSTRT_6") (pintype "bidirectional"))
      (node (ref "U7") (pin "9") (pinfunction "GND_9") (pintype "bidirectional"))
      (node (ref "U8") (pin "11") (pinfunction "TEST_11") (pintype "bidirectional"))
      (node (ref "U8") (pin "EP") (pinfunction "GND_EP") (pintype "bidirectional"))
    )
    (net (code "36") (name "Net-(C1-Pad1)") (class "Default")
      (node (ref "C1") (pin "1") (pinfunction "1_1") (pintype "passive"))
      (node (ref "FB1") (pin "2") (pinfunction "2_2") (pintype "passive"))
      (node (ref "R14") (pin "1") (pinfunction "1_1") (pintype "passive"))
    )
    (net (code "37") (name "Net-(D1-PadA)") (class "Default")
      (node (ref "D1") (pin "A") (pinfunction "A_A") (pintype "passive"))
      (node (ref "R11") (pin "1") (pinfunction "1_1") (pintype "passive"))
    )
    (net (code "38") (name "Net-(J2-SIGNAL)") (class "Default")
      (node (ref "FB1") (pin "1") (pinfunction "1_1") (pintype "passive"))
      (node (ref "J2") (pin "FEED") (pinfunction "SIGNAL_FEED") (pintype "bidirectional"))
      (node (ref "U3") (pin "2") (pinfunction "RF_IN_2") (pintype "bidirectional"))
    )
    (net (code "39") (name "Net-(J5-+)") (class "Default")
      (node (ref "C23") (pin "1") (pinfunction "1_1") (pintype "passive"))
      (node (ref "D4") (pin "C") (pinfunction "C_C") (pintype "passive"))
      (node (ref "J3") (pin "1") (pinfunction "1_1") (pintype "passive"))
      (node (ref "J5") (pin "2") (pinfunction "+_2") (pintype "bidirectional"))
      (node (ref "R31") (pin "1") (pinfunction "1_1") (pintype "passive"))
    )
    (net (code "40") (name "Net-(J7-+)") (class "Default")
      (node (ref "J7") (pin "2") (pinfunction "+_2") (pintype "bidirectional"))
      (node (ref "MEAS2") (pin "1") (pinfunction "1_1") (pintype "passive"))
      (node (ref "MEAS2") (pin "3") (pinfunction "1_3") (pintype "passive"))
    )
    (net (code "41") (name "Net-(JP7-Pad1)") (class "Default")
      (node (ref "JP7") (pin "1") (pinfunction "1_1") (pintype "passive"))
      (node (ref "R12") (pin "2") (pinfunction "2_2") (pintype "passive"))
    )
    (net (code "42") (name "Net-(JP7-Pad3)") (class "Default")
      (node (ref "JP7") (pin "3") (pinfunction "3_3") (pintype "passive"))
      (node (ref "R7") (pin "2") (pinfunction "2_2") (pintype "passive"))
    )
    (net (code "43") (name "Net-(Q2A-B)") (class "Default")
      (node (ref "Q2") (pin "5") (pinfunction "B_5") (pintype "passive"))
      (node (ref "R23") (pin "2") (pinfunction "2_2") (pintype "passive"))
    )
    (net (code "44") (name "Net-(Q2A-E)") (class "Default")
      (node (ref "Q2") (pin "4") (pinfunction "E_4") (pintype "passive"))
      (node (ref "R29") (pin "1") (pinfunction "1_1") (pintype "passive"))
      (node (ref "U6") (pin "14") (pinfunction "~{RTS}_14") (pintype "bidirectional"))
    )
    (net (code "45") (name "Net-(Q2B-B)") (class "Default")
      (node (ref "Q2") (pin "2") (pinfunction "B_2") (pintype "passive"))
      (node (ref "R29") (pin "2") (pinfunction "2_2") (pintype "passive"))
    )
    (net (code "46") (name "Net-(Q2B-E)") (class "Default")
      (node (ref "Q2") (pin "1") (pinfunction "E_1") (pintype "passive"))
      (node (ref "R23") (pin "1") (pinfunction "1_1") (pintype "passive"))
      (node (ref "U6") (pin "13") (pinfunction "~{DTR}_13") (pintype "bidirectional"))
    )
    (net (code "47") (name "Net-(Q3A-D)") (class "Default")
      (node (ref "C22") (pin "1") (pinfunction "1_1") (pintype "passive"))
      (node (ref "C23") (pin "2") (pinfunction "2_2") (pintype "passive"))
      (node (ref "Q3") (pin "D1") (pinfunction "D_D1") (pintype "bidirectional"))
      (node (ref "Q3") (pin "G2") (pinfunction "G_G2") (pintype "bidirectional"))
      (node (ref "R26") (pin "1") (pinfunction "1_1") (pintype "passive"))
    )
    (net (code "48") (name "Net-(R2A-1)") (class "Default")
      (node (ref "R2") (pin "P1") (pinfunction "1_P1") (pintype "passive"))
      (node (ref "U3") (pin "53") (pinfunction "TIMEPULSE_53") (pintype "bidirectional"))
    )
    (net (code "49") (name "Net-(R2B-1)") (class "Default")
      (node (ref "R2") (pin "P2") (pinfunction "1_P2") (pintype "passive"))
      (node (ref "U3") (pin "51") (pinfunction "EXTINT_51") (pintype "bidirectional"))
    )
    (net (code "50") (name "Net-(R2C-1)") (class "Default")
      (node (ref "R2") (pin "P3") (pinfunction "1_P3") (pintype "passive"))
      (node (ref "U3") (pin "50") (pinfunction "~{SAFEBOOT}_50") (pintype "bidirectional"))
    )
    (net (code "51") (name "Net-(R2D-1)") (class "Default")
      (node (ref "R2") (pin "P4") (pinfunction "1_P4") (pintype "passive"))
      (node (ref "U3") (pin "49") (pinfunction "~{RESET}_49") (pintype "bidirectional"))
    )
    (net (code "52") (name "Net-(R4A-2)") (class "Default")
      (node (ref "R4") (pin "P8") (pinfunction "2_P8") (pintype "passive"))
      (node (ref "U3") (pin "19") (pinfunction "GEO_STAT_19") (pintype "bidirectional"))
    )
    (net (code "53") (name "Net-(R4B-2)") (class "Default")
      (node (ref "R4") (pin "P7") (pinfunction "2_P7") (pintype "passive"))
      (node (ref "U3") (pin "20") (pinfunction "RTK_STAT_20") (pintype "bidirectional"))
    )
    (net (code "54") (name "Net-(R4C-2)") (class "Default")
      (node (ref "R4") (pin "P6") (pinfunction "2_P6") (pintype "passive"))
      (node (ref "U3") (pin "26") (pinfunction "RX2_26") (pintype "bidirectional"))
    )
    (net (code "55") (name "Net-(R4D-2)") (class "Default")
      (node (ref "R4") (pin "P5") (pinfunction "2_P5") (pintype "passive"))
      (node (ref "U3") (pin "27") (pinfunction "TX2_27") (pintype "bidirectional"))
    )
    (net (code "56") (name "Net-(R9A-1)") (class "Default")
      (node (ref "R9") (pin "P1") (pinfunction "1_P1") (pintype "passive"))
      (node (ref "U3") (pin "46") (pinfunction "TX_READY_46") (pintype "bidirectional"))
    )
    (net (code "57") (name "Net-(R9B-1)") (class "Default")
      (node (ref "R9") (pin "P2") (pinfunction "1_P2") (pintype "passive"))
      (node (ref "U3") (pin "45") (pinfunction "SCL/CLK_45") (pintype "bidirectional"))
    )
    (net (code "58") (name "Net-(R9C-1)") (class "Default")
      (node (ref "R9") (pin "P3") (pinfunction "1_P3") (pintype "passive"))
      (node (ref "U3") (pin "44") (pinfunction "SDA/~{CS}_44") (pintype "bidirectional"))
    )
    (net (code "59") (name "Net-(R9D-1)") (class "Default")
      (node (ref "R9") (pin "P4") (pinfunction "1_P4") (pintype "passive"))
      (node (ref "U3") (pin "43") (pinfunction "RX/MOSI_43") (pintype "bidirectional"))
    )
    (net (code "60") (name "Net-(R10-Pad2)") (class "Default")
      (node (ref "R10") (pin "2") (pinfunction "2_2") (pintype "bidirectional"))
      (node (ref "R30") (pin "2") (pinfunction "2_2") (pintype "passive"))
      (node (ref "R8") (pin "2") (pinfunction "2_2") (pintype "passive"))
    )
    (net (code "61") (name "Net-(U3-TX{slash}MISO)") (class "Default")
      (node (ref "R3") (pin "1") (pinfunction "1_1") (pintype "passive"))
      (node (ref "U3") (pin "42") (pinfunction "TX/MISO_42") (pintype "bidirectional"))
    )
    (net (code "62") (name "Net-(U3-USB_D+)") (class "Default")
      (node (ref "R27") (pin "2") (pinfunction "2_2") (pintype "passive"))
      (node (ref "U3") (pin "40") (pinfunction "USB_D+_40") (pintype "bidirectional"))
    )
    (net (code "63") (name "Net-(U3-USB_D-)") (class "Default")
      (node (ref "R28") (pin "2") (pinfunction "2_2") (pintype "passive"))
      (node (ref "U3") (pin "39") (pinfunction "USB_D-_39") (pintype "bidirectional"))
    )
    (net (code "64") (name "Net-(U3-V_RF)") (class "Default")
      (node (ref "R14") (pin "2") (pinfunction "2_2") (pintype "passive"))
      (node (ref "U3") (pin "7") (pinfunction "V_RF_7") (pintype "bidirectional"))
    )
    (net (code "65") (name "Net-(U8-CRFILT)") (class "Default")
      (node (ref "C24") (pin "1") (pinfunction "1_1") (pintype "passive"))
      (node (ref "U8") (pin "14") (pinfunction "CRFILT_14") (pintype "bidirectional"))
    )
    (net (code "66") (name "Net-(U8-HS_IND)") (class "Default")
      (node (ref "R17") (pin "2") (pinfunction "2_2") (pintype "passive"))
      (node (ref "U8") (pin "25") (pinfunction "HS_IND_25") (pintype "bidirectional"))
    )
    (net (code "67") (name "Net-(U8-PLLFILT)") (class "Default")
      (node (ref "C21") (pin "1") (pinfunction "1_1") (pintype "passive"))
      (node (ref "U8") (pin "34") (pinfunction "PLLFILT_34") (pintype "bidirectional"))
    )
    (net (code "68") (name "Net-(U8-RBIAS)") (class "Default")
      (node (ref "R5") (pin "1") (pinfunction "1_1") (pintype "passive"))
      (node (ref "U8") (pin "35") (pinfunction "RBIAS_35") (pintype "bidirectional"))
    )
    (net (code "69") (name "Net-(U8-SUSP_IND)") (class "Default")
      (node (ref "R16") (pin "2") (pinfunction "2_2") (pintype "passive"))
      (node (ref "U8") (pin "28") (pinfunction "SUSP_IND_28") (pintype "bidirectional"))
    )
    (net (code "70") (name "Net-(U8-USBDM_UP)") (class "Default")
      (node (ref "R25") (pin "2") (pinfunction "2_2") (pintype "passive"))
      (node (ref "U8") (pin "30") (pinfunction "USBDM_UP_30") (pintype "bidirectional"))
    )
    (net (code "71") (name "Net-(U8-USBDP_UP)") (class "Default")
      (node (ref "R32") (pin "2") (pinfunction "2_2") (pintype "passive"))
      (node (ref "U8") (pin "31") (pinfunction "USBDP_UP_31") (pintype "bidirectional"))
    )
    (net (code "72") (name "Net-(U8-XTALIN)") (class "Default")
      (node (ref "C9") (pin "2") (pinfunction "2_2") (pintype "passive"))
      (node (ref "R13") (pin "2") (pinfunction "2_2") (pintype "passive"))
      (node (ref "U8") (pin "33") (pinfunction "XTALIN_33") (pintype "bidirectional"))
      (node (ref "Y1") (pin "3") (pinfunction "2_3") (pintype "passive"))
    )
    (net (code "73") (name "Net-(U8-XTALOUT)") (class "Default")
      (node (ref "C19") (pin "2") (pinfunction "2_2") (pintype "passive"))
      (node (ref "R13") (pin "1") (pinfunction "1_1") (pintype "passive"))
      (node (ref "U8") (pin "32") (pinfunction "XTALOUT_32") (pintype "bidirectional"))
      (node (ref "Y1") (pin "1") (pinfunction "1_1") (pintype "passive"))
    )
    (net (code "74") (name "Net-(U8-~{RESET})") (class "Default")
      (node (ref "C28") (pin "1") (pinfunction "1_1") (pintype "passive"))
      (node (ref "R18") (pin "1") (pinfunction "1_1") (pintype "passive"))
      (node (ref "U8") (pin "26") (pinfunction "~{RESET}_26") (pintype "bidirectional"))
    )
    (net (code "75") (name "Net-(U10-PROG)") (class "Default")
      (node (ref "R6") (pin "2") (pinfunction "2_2") (pintype "passive"))
      (node (ref "U10") (pin "6") (pinfunction "PROG_6") (pintype "bidirectional"))
    )
    (net (code "76") (name "Net-(U10-THERM)") (class "Default")
      (node (ref "R8") (pin "1") (pinfunction "1_1") (pintype "passive"))
      (node (ref "U10") (pin "8") (pinfunction "THERM_8") (pintype "bidirectional"))
    )
    (net (code "77") (name "USB_DM") (class "Default")
      (node (ref "J18") (pin "8") (pinfunction "8_8") (pintype "bidirectional"))
      (node (ref "R25") (pin "1") (pinfunction "1_1") (pintype "passive"))
    )
    (net (code "78") (name "USB_DP") (class "Default")
      (node (ref "J18") (pin "7") (pinfunction "7_7") (pintype "bidirectional"))
      (node (ref "R32") (pin "1") (pinfunction "1_1") (pintype "passive"))
    )
    (net (code "79") (name "VBUS_DET") (class "Default")
      (node (ref "C29") (pin "1") (pinfunction "1_1") (pintype "passive"))
      (node (ref "R19") (pin "2") (pinfunction "2_2") (pintype "passive"))
      (node (ref "R21") (pin "1") (pinfunction "1_1") (pintype "passive"))
      (node (ref "U8") (pin "27") (pinfunction "VBUS_DET_27") (pintype "bidirectional"))
    )
    (net (code "80") (name "VOUT") (class "Default")
      (node (ref "C20") (pin "1") (pinfunction "1_1") (pintype "passive"))
      (node (ref "C27") (pin "1") (pinfunction "1_1") (pintype "passive"))
      (node (ref "C6") (pin "1") (pinfunction "1_1") (pintype "passive"))
      (node (ref "Q3") (pin "D2") (pinfunction "D_D2") (pintype "bidirectional"))
      (node (ref "R22") (pin "2") (pinfunction "2_2") (pintype "passive"))
      (node (ref "U12") (pin "1") (pinfunction "IN_1") (pintype "input"))
      (node (ref "U2") (pin "1") (pinfunction "IN_1") (pintype "input"))
      (node (ref "U2") (pin "3") (pinfunction "EN_3") (pintype "input"))
    )
    (net (code "81") (name "V_BATT") (class "Default")
      (node (ref "C15") (pin "1") (pinfunction "1_1") (pintype "passive"))
      (node (ref "C17") (pin "1") (pinfunction "1_1") (pintype "passive"))
      (node (ref "C3") (pin "1") (pinfunction "1_1") (pintype "passive"))
      (node (ref "D7") (pin "A") (pinfunction "A_A") (pintype "passive"))
      (node (ref "J15") (pin "6") (pinfunction "6_6") (pintype "bidirectional"))
      (node (ref "J15") (pin "7") (pinfunction "7_7") (pintype "bidirectional"))
      (node (ref "J15") (pin "8") (pinfunction "8_8") (pintype "bidirectional"))
      (node (ref "J15") (pin "9") (pinfunction "9_9") (pintype "bidirectional"))
      (node (ref "MEAS2") (pin "2") (pinfunction "2_2") (pintype "passive"))
      (node (ref "MEAS2") (pin "4") (pinfunction "2_4") (pintype "passive"))
      (node (ref "U10") (pin "10") (pinfunction "VBAT_10") (pintype "bidirectional"))
      (node (ref "U10") (pin "9") (pinfunction "VBAT_9") (pintype "bidirectional"))
      (node (ref "U4") (pin "1") (pinfunction "IN_1") (pintype "input"))
      (node (ref "U4") (pin "3") (pinfunction "EN_3") (pintype "input"))
      (node (ref "U7") (pin "2") (pinfunction "CELL_2") (pintype "input"))
      (node (ref "U7") (pin "3") (pinfunction "VDD_3") (pintype "bidirectional"))
    )
    (net (code "82") (name "V_RAW") (class "Default")
      (node (ref "C16") (pin "1") (pinfunction "1_1") (pintype "passive"))
      (node (ref "C22") (pin "2") (pinfunction "2_2") (pintype "passive"))
      (node (ref "D2") (pin "C") (pinfunction "C_C") (pintype "passive"))
      (node (ref "D7") (pin "C") (pinfunction "C_C") (pintype "passive"))
      (node (ref "Q3") (pin "S2") (pinfunction "S_S2") (pintype "bidirectional"))
      (node (ref "R26") (pin "2") (pinfunction "2_2") (pintype "passive"))
      (node (ref "R31") (pin "2") (pinfunction "2_2") (pintype "passive"))
      (node (ref "U10") (pin "1") (pinfunction "VDD_1") (pintype "bidirectional"))
      (node (ref "U10") (pin "2") (pinfunction "VDD_2") (pintype "bidirectional"))
    )
    (net (code "83") (name "V_USB") (class "Default")
      (node (ref "D2") (pin "A") (pinfunction "A_A") (pintype "passive"))
      (node (ref "J10") (pin "1") (pinfunction "1_1") (pintype "bidirectional"))
      (node (ref "J15") (pin "1") (pinfunction "1_1") (pintype "bidirectional"))
      (node (ref "J15") (pin "2") (pinfunction "2_2") (pintype "bidirectional"))
      (node (ref "J15") (pin "3") (pinfunction "3_3") (pintype "bidirectional"))
      (node (ref "J15") (pin "4") (pinfunction "4_4") (pintype "bidirectional"))
      (node (ref "R21") (pin "2") (pinfunction "2_2") (pintype "passive"))
    )
    (net (code "84") (name "ZED-RXI2") (class "Default")
      (node (ref "J18") (pin "9") (pinfunction "9_9") (pintype "bidirectional"))
      (node (ref "R4") (pin "P3") (pinfunction "1_P3") (pintype "passive"))
    )
    (net (code "85") (name "ZED-TXO2") (class "Default")
      (node (ref "J18") (pin "10") (pinfunction "10_10") (pintype "bidirectional"))
      (node (ref "R4") (pin "P4") (pinfunction "1_P4") (pintype "passive"))
    )
    (net (code "86") (name "ZED_BACKUP") (class "Default")
      (node (ref "C18") (pin "1") (pinfunction "1_1") (pintype "passive"))
      (node (ref "U3") (pin "36") (pinfunction "V_BKCP_36") (pintype "bidirectional"))
      (node (ref "U4") (pin "5") (pinfunction "OUT_5") (pintype "passive"))
    )
    (net (code "87") (name "ZED_DM") (class "Default")
      (node (ref "R28") (pin "1") (pinfunction "1_1") (pintype "passive"))
      (node (ref "U8") (pin "1") (pinfunction "USBDM_DN1_1") (pintype "bidirectional"))
    )
    (net (code "88") (name "ZED_DP") (class "Default")
      (node (ref "R27") (pin "1") (pinfunction "1_1") (pintype "passive"))
      (node (ref "U8") (pin "2") (pinfunction "USBDP_DN1_2") (pintype "bidirectional"))
    )
    (net (code "89") (name "ZED_EXTINT") (class "Default")
      (node (ref "R2") (pin "P7") (pinfunction "2_P7") (pintype "passive"))
      (node (ref "U1") (pin "5") (pinfunction "Y1_5") (pintype "bidirectional"))
    )
    (net (code "90") (name "ZED_FENCE_STAT") (class "Default")
      (node (ref "R4") (pin "P1") (pinfunction "1_P1") (pintype "passive"))
    )
    (net (code "91") (name "ZED_PPS_STAT") (class "Default")
      (node (ref "J4") (pin "2") (pinfunction "2_2") (pintype "passive"))
      (node (ref "R2") (pin "P8") (pinfunction "2_P8") (pintype "passive"))
      (node (ref "U1") (pin "14") (pinfunction "X1_14") (pintype "bidirectional"))
    )
    (net (code "92") (name "ZED_RTK_STAT") (class "Default")
      (node (ref "R4") (pin "P2") (pinfunction "1_P2") (pintype "passive"))
    )
    (net (code "93") (name "ZED_~{SAFE}") (class "Default")
      (node (ref "R2") (pin "P6") (pinfunction "2_P6") (pintype "passive"))
    )
    (net (code "94") (name "unconnected-(J5-PAD1-PadNC1)") (class "Default")
      (node (ref "J5") (pin "NC1") (pinfunction "PAD1_NC1") (pintype "bidirectional"))
    )
    (net (code "95") (name "unconnected-(J5-PAD2-PadNC2)") (class "Default")
      (node (ref "J5") (pin "NC2") (pinfunction "PAD2_NC2") (pintype "bidirectional"))
    )
    (net (code "96") (name "unconnected-(J7-PAD1-PadNC1)") (class "Default")
      (node (ref "J7") (pin "NC1") (pinfunction "PAD1_NC1") (pintype "bidirectional"))
    )
    (net (code "97") (name "unconnected-(J7-PAD2-PadNC2)") (class "Default")
      (node (ref "J7") (pin "NC2") (pinfunction "PAD2_NC2") (pintype "bidirectional"))
    )
    (net (code "98") (name "unconnected-(J15-Pad5)") (class "Default")
      (node (ref "J15") (pin "5") (pinfunction "5_5") (pintype "bidirectional"))
    )
    (net (code "99") (name "unconnected-(U2-NC-Pad4)") (class "Default")
      (node (ref "U2") (pin "4") (pinfunction "NC_4") (pintype "no_connect"))
    )
    (net (code "100") (name "unconnected-(U3-ANT_DETECT-Pad4)") (class "Default")
      (node (ref "U3") (pin "4") (pinfunction "ANT_DETECT_4") (pintype "bidirectional"))
    )
    (net (code "101") (name "unconnected-(U3-ANT_OFF-Pad5)") (class "Default")
      (node (ref "U3") (pin "5") (pinfunction "ANT_OFF_5") (pintype "bidirectional"))
    )
    (net (code "102") (name "unconnected-(U3-D_SEL-Pad47)") (class "Default")
      (node (ref "U3") (pin "47") (pinfunction "D_SEL_47") (pintype "bidirectional"))
    )
    (net (code "103") (name "unconnected-(U3-~{ANT_SHORT}-Pad6)") (class "Default")
      (node (ref "U3") (pin "6") (pinfunction "~{ANT_SHORT}_6") (pintype "bidirectional"))
    )
    (net (code "104") (name "unconnected-(U4-NC-Pad4)") (class "Default")
      (node (ref "U4") (pin "4") (pinfunction "NC_4") (pintype "no_connect"))
    )
    (net (code "105") (name "unconnected-(U5-SCK{slash}IO6-Pad20)") (class "Default")
      (node (ref "U5") (pin "20") (pinfunction "SCK/IO6_20") (pintype "bidirectional"))
    )
    (net (code "106") (name "unconnected-(U5-SCS{slash}IO11-Pad19)") (class "Default")
      (node (ref "U5") (pin "19") (pinfunction "SCS/IO11_19") (pintype "bidirectional"))
    )
    (net (code "107") (name "unconnected-(U5-SDI{slash}IO8-Pad22)") (class "Default")
      (node (ref "U5") (pin "22") (pinfunction "SDI/IO8_22") (pintype "bidirectional"))
    )
    (net (code "108") (name "unconnected-(U5-SDO{slash}IO7-Pad21)") (class "Default")
      (node (ref "U5") (pin "21") (pinfunction "SDO/IO7_21") (pintype "bidirectional"))
    )
    (net (code "109") (name "unconnected-(U5-SHD{slash}IO9-Pad17)") (class "Default")
      (node (ref "U5") (pin "17") (pinfunction "SHD/IO9_17") (pintype "bidirectional"))
    )
    (net (code "110") (name "unconnected-(U5-SWP{slash}IO10-Pad18)") (class "Default")
      (node (ref "U5") (pin "18") (pinfunction "SWP/IO10_18") (pintype "bidirectional"))
    )
    (net (code "111") (name "unconnected-(U6-R232-Pad15)") (class "Default")
      (node (ref "U6") (pin "15") (pinfunction "R232_15") (pintype "bidirectional"))
    )
    (net (code "112") (name "unconnected-(U6-~{CTS}-Pad9)") (class "Default")
      (node (ref "U6") (pin "9") (pinfunction "~{CTS}_9") (pintype "bidirectional"))
    )
    (net (code "113") (name "unconnected-(U6-~{DCD}-Pad12)") (class "Default")
      (node (ref "U6") (pin "12") (pinfunction "~{DCD}_12") (pintype "bidirectional"))
    )
    (net (code "114") (name "unconnected-(U6-~{DSR}-Pad10)") (class "Default")
      (node (ref "U6") (pin "10") (pinfunction "~{DSR}_10") (pintype "bidirectional"))
    )
    (net (code "115") (name "unconnected-(U6-~{RI}-Pad11)") (class "Default")
      (node (ref "U6") (pin "11") (pinfunction "~{RI}_11") (pintype "bidirectional"))
    )
    (net (code "116") (name "unconnected-(U8-PRTPWR1-Pad12)") (class "Default")
      (node (ref "U8") (pin "12") (pinfunction "PRTPWR1_12") (pintype "bidirectional"))
    )
    (net (code "117") (name "unconnected-(U8-PRTPWR2-Pad16)") (class "Default")
      (node (ref "U8") (pin "16") (pinfunction "PRTPWR2_16") (pintype "bidirectional"))
    )
    (net (code "118") (name "unconnected-(U8-PRTPWR3-Pad18)") (class "Default")
      (node (ref "U8") (pin "18") (pinfunction "PRTPWR3_18") (pintype "bidirectional"))
    )
    (net (code "119") (name "unconnected-(U8-PRTPWR4-Pad20)") (class "Default")
      (node (ref "U8") (pin "20") (pinfunction "PRTPWR4_20") (pintype "bidirectional"))
    )
    (net (code "120") (name "unconnected-(U8-USBDM_DN3-Pad6)") (class "Default")
      (node (ref "U8") (pin "6") (pinfunction "USBDM_DN3_6") (pintype "bidirectional"))
    )
    (net (code "121") (name "unconnected-(U8-USBDM_DN4-Pad8)") (class "Default")
      (node (ref "U8") (pin "8") (pinfunction "USBDM_DN4_8") (pintype "bidirectional"))
    )
    (net (code "122") (name "unconnected-(U8-USBDP_DN3-Pad7)") (class "Default")
      (node (ref "U8") (pin "7") (pinfunction "USBDP_DN3_7") (pintype "bidirectional"))
    )
    (net (code "123") (name "unconnected-(U8-USBDP_DN4-Pad9)") (class "Default")
      (node (ref "U8") (pin "9") (pinfunction "USBDP_DN4_9") (pintype "bidirectional"))
    )
    (net (code "124") (name "unconnected-(U8-~{OCS1}-Pad13)") (class "Default")
      (node (ref "U8") (pin "13") (pinfunction "~{OCS1}_13") (pintype "bidirectional"))
    )
    (net (code "125") (name "unconnected-(U8-~{OCS2}-Pad17)") (class "Default")
      (node (ref "U8") (pin "17") (pinfunction "~{OCS2}_17") (pintype "bidirectional"))
    )
    (net (code "126") (name "unconnected-(U8-~{OCS3}-Pad19)") (class "Default")
      (node (ref "U8") (pin "19") (pinfunction "~{OCS3}_19") (pintype "bidirectional"))
    )
    (net (code "127") (name "unconnected-(U8-~{OCS4}-Pad21)") (class "Default")
      (node (ref "U8") (pin "21") (pinfunction "~{OCS4}_21") (pintype "bidirectional"))
    )
    (net (code "128") (name "unconnected-(U10-STAT2-Pad4)") (class "Default")
      (node (ref "U10") (pin "4") (pinfunction "STAT2_4") (pintype "bidirectional"))
    )
    (net (code "129") (name "unconnected-(U10-~{PG}-Pad7)") (class "Default")
      (node (ref "U10") (pin "7") (pinfunction "~{PG}_7") (pintype "bidirectional"))
    )
    (net (code "130") (name "unconnected-(U12-NC-Pad4)") (class "Default")
      (node (ref "U12") (pin "4") (pinfunction "NC_4") (pintype "no_connect"))
    )
  )
)
